# XTJ-Prime_2S1P.net
KiCad netlist of a schematic drawn in Altium Designer
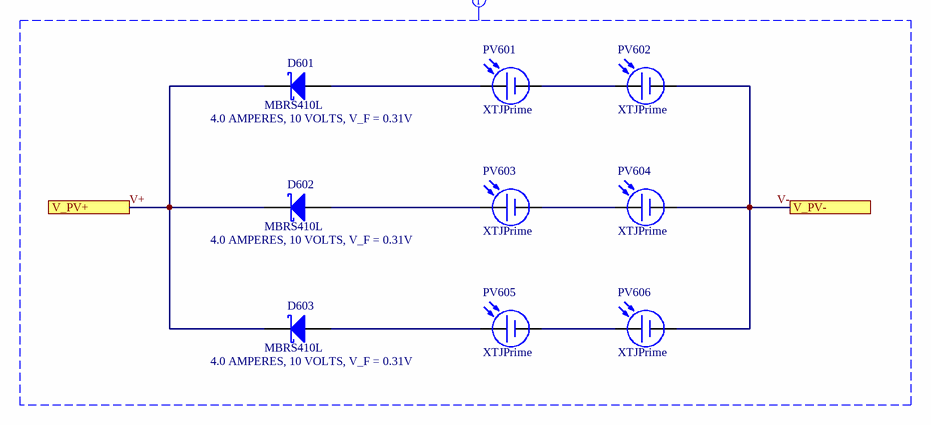
[diagram p0: XTJ-Prime_2S1P.SchDoc]

(export (version "E")
  (design (tool "Eeschema 10.0.6"))
  (components
    (comp (ref "D601")
      (value "MBRS410L")
      (footprint "ONS-875")
      (description "SCHOTTKY BARRIER\r\nRECTIFIERS\r\n4.0 AMPERES, 10 VOLTS, V_F = 0.31V")
      (fields (field (name "PART NUMBER") "PXX-ONS-00003") (field (name "PUBLISHER") "AlbertaSat"))
      (libsource (lib "Database") (part "D Schottky"))
    )
    (comp (ref "D602")
      (value "MBRS410L")
      (footprint "ONS-875")
      (description "SCHOTTKY BARRIER\r\nRECTIFIERS\r\n4.0 AMPERES, 10 VOLTS, V_F = 0.31V")
      (fields (field (name "PART NUMBER") "PXX-ONS-00003") (field (name "PUBLISHER") "AlbertaSat"))
      (libsource (lib "Database") (part "D Schottky"))
    )
    (comp (ref "D603")
      (value "MBRS410L")
      (footprint "ONS-875")
      (description "SCHOTTKY BARRIER\r\nRECTIFIERS\r\n4.0 AMPERES, 10 VOLTS, V_F = 0.31V")
      (fields (field (name "PART NUMBER") "PXX-ONS-00003") (field (name "PUBLISHER") "AlbertaSat"))
      (libsource (lib "Database") (part "D Schottky"))
    )
    (comp (ref "PV601")
      (value "XTJPrime")
      (footprint "XTJ Prime")
      (fields
        (field (name "PART NUMBER") "PBT-SPEC-00002")
        (field (name "MANUFACTURER PART NUMBER") "Spectrolab")
        (field (name "PUBLISHER") "AlbertaSat")
      )
      (libsource (lib "Database") (part "SolarCell"))
    )
    (comp (ref "PV602")
      (value "XTJPrime")
      (footprint "XTJ Prime")
      (fields
        (field (name "PART NUMBER") "PBT-SPEC-00002")
        (field (name "MANUFACTURER PART NUMBER") "Spectrolab")
        (field (name "PUBLISHER") "AlbertaSat")
      )
      (libsource (lib "Database") (part "SolarCell"))
    )
    (comp (ref "PV603")
      (value "XTJPrime")
      (footprint "XTJ Prime")
      (fields
        (field (name "PART NUMBER") "PBT-SPEC-00002")
        (field (name "MANUFACTURER PART NUMBER") "Spectrolab")
        (field (name "PUBLISHER") "AlbertaSat")
      )
      (libsource (lib "Database") (part "SolarCell"))
    )
    (comp (ref "PV604")
      (value "XTJPrime")
      (footprint "XTJ Prime")
      (fields
        (field (name "PART NUMBER") "PBT-SPEC-00002")
        (field (name "MANUFACTURER PART NUMBER") "Spectrolab")
        (field (name "PUBLISHER") "AlbertaSat")
      )
      (libsource (lib "Database") (part "SolarCell"))
    )
    (comp (ref "PV605")
      (value "XTJPrime")
      (footprint "XTJ Prime")
      (fields
        (field (name "PART NUMBER") "PBT-SPEC-00002")
        (field (name "MANUFACTURER PART NUMBER") "Spectrolab")
        (field (name "PUBLISHER") "AlbertaSat")
      )
      (libsource (lib "Database") (part "SolarCell"))
    )
    (comp (ref "PV606")
      (value "XTJPrime")
      (footprint "XTJ Prime")
      (fields
        (field (name "PART NUMBER") "PBT-SPEC-00002")
        (field (name "MANUFACTURER PART NUMBER") "Spectrolab")
        (field (name "PUBLISHER") "AlbertaSat")
      )
      (libsource (lib "Database") (part "SolarCell"))
    )
  )
  (nets
    (net (code "1") (name "/V+") (class "Default")
      (node (ref "D601") (pin "2") (pinfunction "2_2") (pintype "passive"))
      (node (ref "D602") (pin "2") (pinfunction "2_2") (pintype "passive"))
      (node (ref "D603") (pin "2") (pinfunction "2_2") (pintype "passive"))
    )
    (net (code "2") (name "/V-") (class "Default")
      (node (ref "PV602") (pin "2") (pinfunction "Neg_2") (pintype "passive"))
      (node (ref "PV604") (pin "2") (pinfunction "Neg_2") (pintype "passive"))
      (node (ref "PV606") (pin "2") (pinfunction "Neg_2") (pintype "passive"))
    )
    (net (code "3") (name "Net-(PV601-Neg)") (class "Default")
      (node (ref "PV601") (pin "2") (pinfunction "Neg_2") (pintype "passive"))
      (node (ref "PV602") (pin "1") (pinfunction "Pos_1") (pintype "passive"))
    )
    (net (code "4") (name "Net-(PV601-Pos)") (class "Default")
      (node (ref "D601") (pin "1") (pinfunction "1_1") (pintype "passive"))
      (node (ref "PV601") (pin "1") (pinfunction "Pos_1") (pintype "passive"))
    )
    (net (code "5") (name "Net-(PV603-Neg)") (class "Default")
      (node (ref "PV603") (pin "2") (pinfunction "Neg_2") (pintype "passive"))
      (node (ref "PV604") (pin "1") (pinfunction "Pos_1") (pintype "passive"))
    )
    (net (code "6") (name "Net-(PV603-Pos)") (class "Default")
      (node (ref "D602") (pin "1") (pinfunction "1_1") (pintype "passive"))
      (node (ref "PV603") (pin "1") (pinfunction "Pos_1") (pintype "passive"))
    )
    (net (code "7") (name "Net-(PV605-Neg)") (class "Default")
      (node (ref "PV605") (pin "2") (pinfunction "Neg_2") (pintype "passive"))
      (node (ref "PV606") (pin "1") (pinfunction "Pos_1") (pintype "passive"))
    )
    (net (code "8") (name "Net-(PV605-Pos)") (class "Default")
      (node (ref "D603") (pin "1") (pinfunction "1_1") (pintype "passive"))
      (node (ref "PV605") (pin "1") (pinfunction "Pos_1") (pintype "passive"))
    )
  )
)
